# SW6106_C_LED.net
KiCad netlist of a schematic drawn in Altium Designer
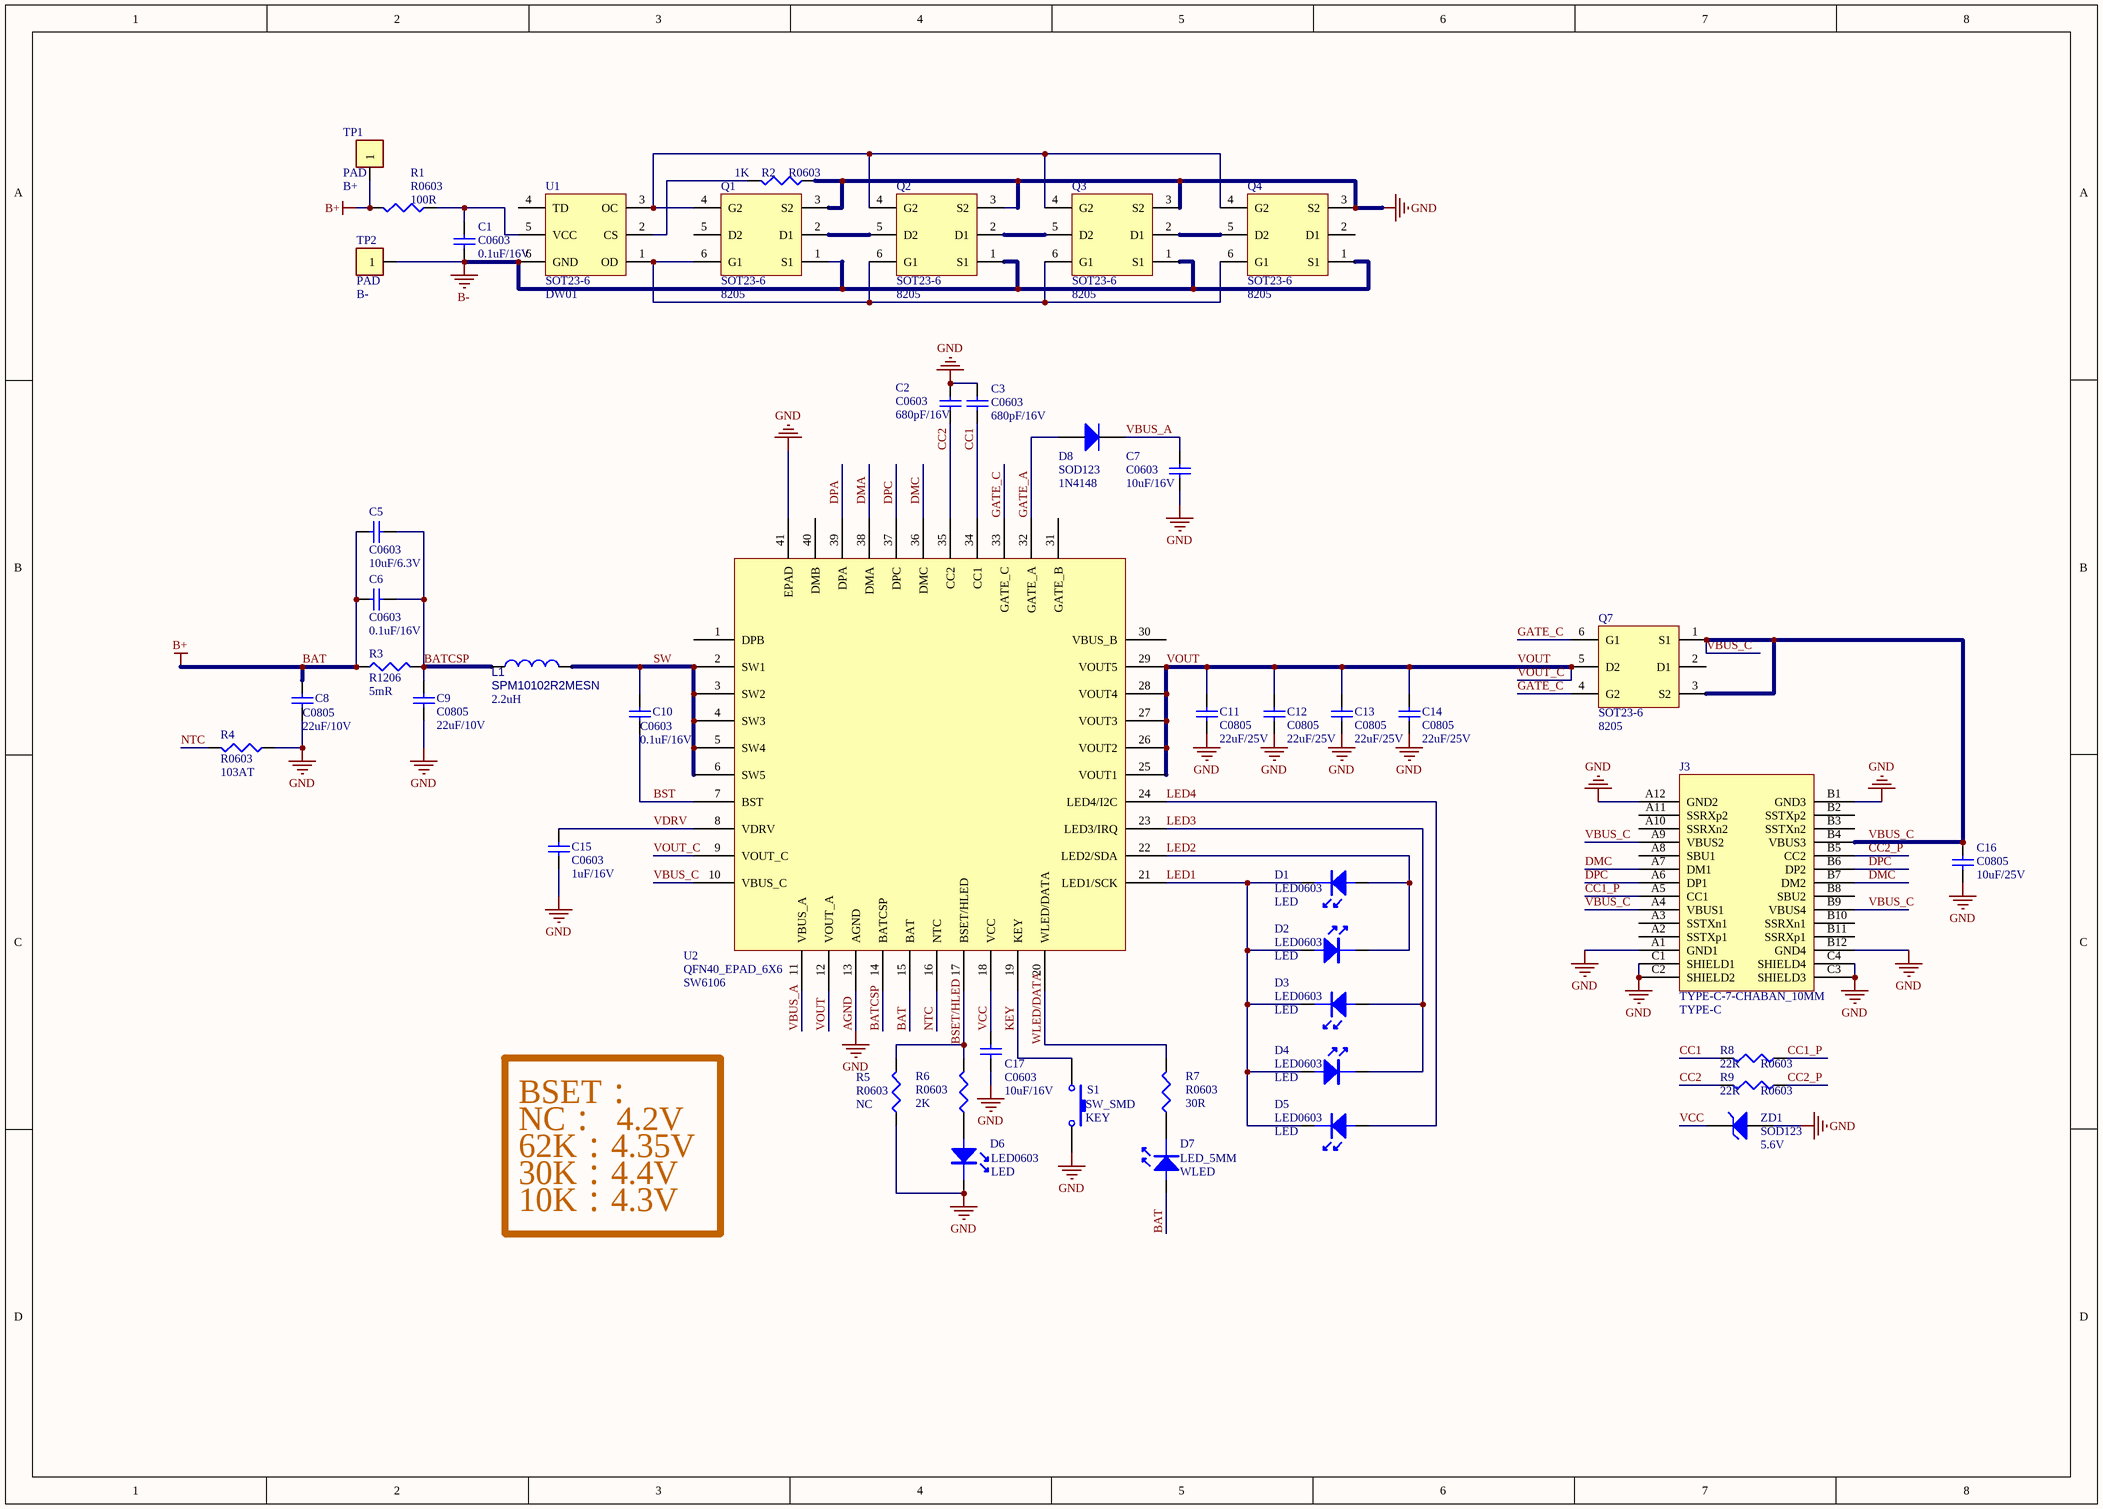
[diagram p0: SW6106+C+LED.SchDoc]

(export (version "E")
  (design (tool "Eeschema 10.0.6"))
  (components
    (comp (ref "C1")
      (value "C0603")
      (footprint "C0603")
      (description "Capacitor")
      (fields (field (name "ALTIUM_VALUE") "0.1uF/16V") (field (name "PUBLISHER") "Altium Limited"))
      (libsource (lib "*") (part "Cap"))
    )
    (comp (ref "C2")
      (value "C0603")
      (footprint "C0603")
      (description "Capacitor")
      (fields (field (name "ALTIUM_VALUE") "680pF/16V") (field (name "PUBLISHER") "Altium Limited"))
      (libsource (lib "*") (part "CAP0603"))
    )
    (comp (ref "C3")
      (value "C0603")
      (footprint "C0603")
      (description "Capacitor")
      (fields (field (name "ALTIUM_VALUE") "680pF/16V") (field (name "PUBLISHER") "Altium Limited"))
      (libsource (lib "*") (part "CAP0603"))
    )
    (comp (ref "C5")
      (value "C0603")
      (footprint "C0603")
      (description "Capacitor")
      (fields (field (name "ALTIUM_VALUE") "10uF/6.3V") (field (name "PUBLISHER") "Altium Limited"))
      (libsource (lib "*") (part "CAP0603"))
    )
    (comp (ref "C6")
      (value "C0603")
      (footprint "C0603")
      (description "Capacitor")
      (fields (field (name "ALTIUM_VALUE") "0.1uF/16V") (field (name "PUBLISHER") "Altium Limited"))
      (libsource (lib "*") (part "CAP0603"))
    )
    (comp (ref "C7")
      (value "C0603")
      (footprint "C0603")
      (description "Capacitor")
      (fields (field (name "ALTIUM_VALUE") "10uF/16V") (field (name "PUBLISHER") "Altium Limited"))
      (libsource (lib "*") (part "CAP0603"))
    )
    (comp (ref "C8")
      (value "C0805")
      (footprint "C0805")
      (description "Capacitor")
      (fields (field (name "ALTIUM_VALUE") "22uF/10V") (field (name "PUBLISHER") "Altium Limited"))
      (libsource (lib "*") (part "CAP0805"))
    )
    (comp (ref "C9")
      (value "C0805")
      (footprint "C0805")
      (description "Capacitor")
      (fields (field (name "ALTIUM_VALUE") "22uF/10V") (field (name "PUBLISHER") "Altium Limited"))
      (libsource (lib "*") (part "CAP0805"))
    )
    (comp (ref "C10")
      (value "C0603")
      (footprint "C0603")
      (description "Capacitor")
      (fields (field (name "ALTIUM_VALUE") "0.1uF/16V") (field (name "PUBLISHER") "Altium Limited"))
      (libsource (lib "*") (part "CAP0603"))
    )
    (comp (ref "C11")
      (value "C0805")
      (footprint "C0805")
      (description "Capacitor")
      (fields (field (name "ALTIUM_VALUE") "22uF/25V") (field (name "PUBLISHER") "Altium Limited"))
      (libsource (lib "*") (part "CAP0805"))
    )
    (comp (ref "C12")
      (value "C0805")
      (footprint "C0805")
      (description "Capacitor")
      (fields (field (name "ALTIUM_VALUE") "22uF/25V") (field (name "PUBLISHER") "Altium Limited"))
      (libsource (lib "*") (part "CAP0805"))
    )
    (comp (ref "C13")
      (value "C0805")
      (footprint "C0805")
      (description "Capacitor")
      (fields (field (name "ALTIUM_VALUE") "22uF/25V") (field (name "PUBLISHER") "Altium Limited"))
      (libsource (lib "*") (part "CAP0805"))
    )
    (comp (ref "C14")
      (value "C0805")
      (footprint "C0805")
      (description "Capacitor")
      (fields (field (name "ALTIUM_VALUE") "22uF/25V") (field (name "PUBLISHER") "Altium Limited"))
      (libsource (lib "*") (part "CAP0805"))
    )
    (comp (ref "C15")
      (value "C0603")
      (footprint "C0603")
      (description "Capacitor")
      (fields (field (name "ALTIUM_VALUE") "1uF/16V") (field (name "PUBLISHER") "Altium Limited"))
      (libsource (lib "*") (part "CAP0603"))
    )
    (comp (ref "C16")
      (value "C0805")
      (footprint "C0805")
      (description "Capacitor")
      (fields (field (name "ALTIUM_VALUE") "10uF/25V") (field (name "PUBLISHER") "Altium Limited"))
      (libsource (lib "*") (part "CAP0603"))
    )
    (comp (ref "C17")
      (value "C0603")
      (footprint "C0603")
      (description "Capacitor")
      (fields (field (name "ALTIUM_VALUE") "10uF/16V") (field (name "PUBLISHER") "Altium Limited"))
      (libsource (lib "*") (part "CAP0603"))
    )
    (comp (ref "D1") (value "LED") (footprint "LED0603") (libsource (lib "*") (part "LED")))
    (comp (ref "D2") (value "LED") (footprint "LED0603") (libsource (lib "*") (part "LED")))
    (comp (ref "D3") (value "LED") (footprint "LED0603") (libsource (lib "*") (part "LED")))
    (comp (ref "D4") (value "LED") (footprint "LED0603") (libsource (lib "*") (part "LED")))
    (comp (ref "D5") (value "LED") (footprint "LED0603") (libsource (lib "*") (part "LED")))
    (comp (ref "D6") (value "LED") (footprint "LED0603") (libsource (lib "*") (part "LED")))
    (comp (ref "D7")
      (value "WLED")
      (footprint "LED_5MM")
      (fields (field (name "FOOTPRINF") "LED_5MM") (field (name "Comment") "LED_5MM"))
      (libsource (lib "*") (part "LED"))
    )
    (comp (ref "D8")
      (value "1N4148")
      (footprint "SOD123")
      (description "High Conductance Fast Diode")
      (fields (field (name "Comment") "Diode 1N4148") (field (name "PUBLISHER") "Altium Limited"))
      (libsource (lib "Miscellaneous Devices") (part "Diode 1N4148"))
    )
    (comp (ref "J3")
      (value "TYPE-C")
      (footprint "TYPE-C-7-CHABAN_10MM")
      (libsource (lib "*") (part "TYPE-C"))
    )
    (comp (ref "L1")
      (value "SPM10102R2MESN")
      (footprint "INDUCTOR_SPM1010")
      (fields (field (name "ALTIUM_VALUE") "2.2uH"))
      (libsource (lib "*") (part "INDUCTOR"))
    )
    (comp (ref "Q1")
      (value "8205")
      (footprint "SOT23-6")
      (fields (field (name "FOOTPRINF") "SOT23-6"))
      (libsource (lib "*") (part "8205B"))
    )
    (comp (ref "Q2")
      (value "8205")
      (footprint "SOT23-6")
      (fields (field (name "FOOTPRINF") "SOT23-6"))
      (libsource (lib "*") (part "8205B"))
    )
    (comp (ref "Q3")
      (value "8205")
      (footprint "SOT23-6")
      (fields (field (name "FOOTPRINF") "SOT23-6"))
      (libsource (lib "*") (part "8205B"))
    )
    (comp (ref "Q4")
      (value "8205")
      (footprint "SOT23-6")
      (fields (field (name "FOOTPRINF") "SOT23-6"))
      (libsource (lib "*") (part "8205B"))
    )
    (comp (ref "Q7")
      (value "8205")
      (footprint "SOT23-6")
      (fields (field (name "FOOTPRINF") "SOT23-6"))
      (libsource (lib "") (part "8205B_1"))
    )
    (comp (ref "R1")
      (value "R0603")
      (footprint "R0603")
      (description "Resistor")
      (fields (field (name "ALTIUM_VALUE") "100R") (field (name "PUBLISHER") "Altium Limited"))
      (libsource (lib "*") (part "Res3"))
    )
    (comp (ref "R2")
      (value "R0603")
      (footprint "R0603")
      (description "Resistor")
      (fields (field (name "ALTIUM_VALUE") "1K") (field (name "PUBLISHER") "Altium Limited"))
      (libsource (lib "*") (part "Res3"))
    )
    (comp (ref "R3")
      (value "R1206")
      (footprint "R1206")
      (description "Resistor")
      (fields (field (name "ALTIUM_VALUE") "5mR") (field (name "PUBLISHER") "Altium Limited"))
      (libsource (lib "*") (part "RES"))
    )
    (comp (ref "R4")
      (value "R0603")
      (footprint "R0603")
      (description "Resistor")
      (fields (field (name "ALTIUM_VALUE") "103AT") (field (name "PUBLISHER") "Altium Limited"))
      (libsource (lib "*") (part "RES"))
    )
    (comp (ref "R5")
      (value "R0603")
      (footprint "R0603")
      (description "Resistor")
      (fields (field (name "ALTIUM_VALUE") "NC") (field (name "PUBLISHER") "Altium Limited"))
      (libsource (lib "*") (part "RES"))
    )
    (comp (ref "R6")
      (value "R0603")
      (footprint "R0603")
      (description "Resistor")
      (fields (field (name "ALTIUM_VALUE") "2K") (field (name "PUBLISHER") "Altium Limited"))
      (libsource (lib "*") (part "RES"))
    )
    (comp (ref "R7")
      (value "R0603")
      (footprint "R0603")
      (description "Resistor")
      (fields (field (name "ALTIUM_VALUE") "30R") (field (name "PUBLISHER") "Altium Limited"))
      (libsource (lib "*") (part "RES"))
    )
    (comp (ref "R8")
      (value "R0603")
      (footprint "R0603")
      (description "Resistor")
      (fields (field (name "ALTIUM_VALUE") "22R") (field (name "PUBLISHER") "Altium Limited"))
      (libsource (lib "*") (part "RES"))
    )
    (comp (ref "R9")
      (value "R0603")
      (footprint "R0603")
      (description "Resistor")
      (fields (field (name "ALTIUM_VALUE") "22R") (field (name "PUBLISHER") "Altium Limited"))
      (libsource (lib "*") (part "RES"))
    )
    (comp (ref "S1")
      (value "KEY")
      (footprint "SW_SMD")
      (fields (field (name "FOOTPRINF") "SW_SMD"))
      (libsource (lib "*") (part "SW K"))
    )
    (comp (ref "TP1") (value "B+") (footprint "PAD") (libsource (lib "*") (part "Test Point")))
    (comp (ref "TP2") (value "B-") (footprint "PAD") (libsource (lib "") (part "Test Point_1")))
    (comp (ref "U1")
      (value "DW01")
      (footprint "SOT23-6")
      (fields (field (name "FOOTPRINF") "SOT23-6"))
      (libsource (lib "*") (part "DW01"))
    )
    (comp (ref "U2")
      (value "SW6106")
      (footprint "QFN40_EPAD_6X6")
      (libsource (lib "TEST") (part "SW6106_AFC"))
    )
    (comp (ref "ZD1")
      (value "SOD123")
      (footprint "SOD-123")
      (description "Zener Diode")
      (fields (field (name "ALTIUM_UNNAMED_1") "5.6V"))
      (libsource (lib "Miscellaneous Devices") (part "D Zener"))
    )
  )
  (nets
    (net (code "1") (name "/BATCSP") (class "Default")
      (node (ref "C5") (pin "2") (pinfunction "2_2") (pintype "passive"))
      (node (ref "C6") (pin "2") (pinfunction "2_2") (pintype "passive"))
      (node (ref "C9") (pin "2") (pinfunction "2_2") (pintype "passive"))
      (node (ref "L1") (pin "1") (pinfunction "1_1") (pintype "passive"))
      (node (ref "R3") (pin "2") (pinfunction "2_2") (pintype "passive"))
      (node (ref "U2") (pin "14") (pinfunction "BATCSP_14") (pintype "passive"))
    )
    (net (code "2") (name "/BSET{slash}HLED") (class "Default")
      (node (ref "R5") (pin "2") (pinfunction "2_2") (pintype "passive"))
      (node (ref "R6") (pin "2") (pinfunction "2_2") (pintype "passive"))
      (node (ref "U2") (pin "17") (pinfunction "BSET/HLED_17") (pintype "passive"))
    )
    (net (code "3") (name "/BST") (class "Default")
      (node (ref "C10") (pin "1") (pinfunction "1_1") (pintype "passive"))
      (node (ref "U2") (pin "7") (pinfunction "BST_7") (pintype "passive"))
    )
    (net (code "4") (name "/CC1") (class "Default")
      (node (ref "C3") (pin "1") (pinfunction "1_1") (pintype "passive"))
      (node (ref "R8") (pin "2") (pinfunction "2_2") (pintype "passive"))
      (node (ref "U2") (pin "34") (pinfunction "CC1_34") (pintype "passive"))
    )
    (net (code "5") (name "/CC1_P") (class "Default")
      (node (ref "J3") (pin "A5") (pinfunction "CC1_A5") (pintype "passive"))
      (node (ref "R8") (pin "1") (pinfunction "1_1") (pintype "passive"))
    )
    (net (code "6") (name "/CC2") (class "Default")
      (node (ref "C2") (pin "1") (pinfunction "1_1") (pintype "passive"))
      (node (ref "R9") (pin "2") (pinfunction "2_2") (pintype "passive"))
      (node (ref "U2") (pin "35") (pinfunction "CC2_35") (pintype "passive"))
    )
    (net (code "7") (name "/CC2_P") (class "Default")
      (node (ref "J3") (pin "B5") (pinfunction "CC2_B5") (pintype "passive"))
      (node (ref "R9") (pin "1") (pinfunction "1_1") (pintype "passive"))
    )
    (net (code "8") (name "/DMA") (class "Default")
      (node (ref "U2") (pin "38") (pinfunction "DMA_38") (pintype "passive"))
    )
    (net (code "9") (name "/DMC") (class "Default")
      (node (ref "J3") (pin "A7") (pinfunction "DM1_A7") (pintype "passive"))
      (node (ref "J3") (pin "B7") (pinfunction "DM2_B7") (pintype "passive"))
      (node (ref "U2") (pin "36") (pinfunction "DMC_36") (pintype "passive"))
    )
    (net (code "10") (name "/DPA") (class "Default")
      (node (ref "U2") (pin "39") (pinfunction "DPA_39") (pintype "passive"))
    )
    (net (code "11") (name "/DPC") (class "Default")
      (node (ref "J3") (pin "A6") (pinfunction "DP1_A6") (pintype "passive"))
      (node (ref "J3") (pin "B6") (pinfunction "DP2_B6") (pintype "passive"))
      (node (ref "U2") (pin "37") (pinfunction "DPC_37") (pintype "passive"))
    )
    (net (code "12") (name "/GATE_A") (class "Default")
      (node (ref "D8") (pin "1") (pinfunction "A_1") (pintype "passive"))
      (node (ref "U2") (pin "32") (pinfunction "GATE_A_32") (pintype "passive"))
    )
    (net (code "13") (name "/GATE_C") (class "Default")
      (node (ref "Q7") (pin "4") (pinfunction "G2_4") (pintype "passive"))
      (node (ref "Q7") (pin "6") (pinfunction "G1_6") (pintype "passive"))
      (node (ref "U2") (pin "33") (pinfunction "GATE_C_33") (pintype "passive"))
    )
    (net (code "14") (name "/KEY") (class "Default")
      (node (ref "S1") (pin "1") (pinfunction "1_1") (pintype "passive"))
      (node (ref "U2") (pin "19") (pinfunction "KEY_19") (pintype "passive"))
    )
    (net (code "15") (name "/LED1") (class "Default")
      (node (ref "D1") (pin "2") (pinfunction "K_2") (pintype "passive"))
      (node (ref "D2") (pin "1") (pinfunction "A_1") (pintype "passive"))
      (node (ref "D3") (pin "2") (pinfunction "K_2") (pintype "passive"))
      (node (ref "D4") (pin "1") (pinfunction "A_1") (pintype "passive"))
      (node (ref "D5") (pin "2") (pinfunction "K_2") (pintype "passive"))
      (node (ref "U2") (pin "21") (pinfunction "LED1/SCK_21") (pintype "passive"))
    )
    (net (code "16") (name "/LED2") (class "Default")
      (node (ref "D1") (pin "1") (pinfunction "A_1") (pintype "passive"))
      (node (ref "D2") (pin "2") (pinfunction "K_2") (pintype "passive"))
      (node (ref "U2") (pin "22") (pinfunction "LED2/SDA_22") (pintype "passive"))
    )
    (net (code "17") (name "/LED3") (class "Default")
      (node (ref "D3") (pin "1") (pinfunction "A_1") (pintype "passive"))
      (node (ref "D4") (pin "2") (pinfunction "K_2") (pintype "passive"))
      (node (ref "U2") (pin "23") (pinfunction "LED3/IRQ_23") (pintype "passive"))
    )
    (net (code "18") (name "/LED4") (class "Default")
      (node (ref "D5") (pin "1") (pinfunction "A_1") (pintype "passive"))
      (node (ref "U2") (pin "24") (pinfunction "LED4/I2C_24") (pintype "passive"))
    )
    (net (code "19") (name "/NTC") (class "Default")
      (node (ref "R4") (pin "2") (pinfunction "2_2") (pintype "passive"))
      (node (ref "U2") (pin "16") (pinfunction "NTC_16") (pintype "passive"))
    )
    (net (code "20") (name "/SW") (class "Default")
      (node (ref "C10") (pin "2") (pinfunction "2_2") (pintype "passive"))
      (node (ref "L1") (pin "2") (pinfunction "2_2") (pintype "passive"))
      (node (ref "U2") (pin "2") (pinfunction "SW1_2") (pintype "passive"))
      (node (ref "U2") (pin "3") (pinfunction "SW2_3") (pintype "passive"))
      (node (ref "U2") (pin "4") (pinfunction "SW3_4") (pintype "passive"))
      (node (ref "U2") (pin "5") (pinfunction "SW4_5") (pintype "passive"))
      (node (ref "U2") (pin "6") (pinfunction "SW5_6") (pintype "passive"))
    )
    (net (code "21") (name "/VBUS_A") (class "Default")
      (node (ref "C7") (pin "2") (pinfunction "2_2") (pintype "passive"))
      (node (ref "D8") (pin "2") (pinfunction "K_2") (pintype "passive"))
      (node (ref "U2") (pin "11") (pinfunction "VBUS_A_11") (pintype "passive"))
    )
    (net (code "22") (name "/VBUS_C") (class "Default")
      (node (ref "C16") (pin "2") (pinfunction "2_2") (pintype "passive"))
      (node (ref "J3") (pin "A4") (pinfunction "VBUS1_A4") (pintype "passive"))
      (node (ref "J3") (pin "A9") (pinfunction "VBUS2_A9") (pintype "passive"))
      (node (ref "J3") (pin "B4") (pinfunction "VBUS3_B4") (pintype "passive"))
      (node (ref "J3") (pin "B9") (pinfunction "VBUS4_B9") (pintype "passive"))
      (node (ref "Q7") (pin "1") (pinfunction "S1_1") (pintype "passive"))
      (node (ref "Q7") (pin "3") (pinfunction "S2_3") (pintype "passive"))
      (node (ref "U2") (pin "10") (pinfunction "VBUS_C_10") (pintype "passive"))
    )
    (net (code "23") (name "/VCC") (class "Default")
      (node (ref "C17") (pin "2") (pinfunction "2_2") (pintype "passive"))
      (node (ref "U2") (pin "18") (pinfunction "VCC_18") (pintype "passive"))
      (node (ref "ZD1") (pin "2") (pinfunction "K_2") (pintype "passive"))
    )
    (net (code "24") (name "/VDRV") (class "Default")
      (node (ref "C15") (pin "2") (pinfunction "2_2") (pintype "passive"))
      (node (ref "U2") (pin "8") (pinfunction "VDRV_8") (pintype "passive"))
    )
    (net (code "25") (name "/VOUT") (class "Default")
      (node (ref "C11") (pin "2") (pinfunction "2_2") (pintype "passive"))
      (node (ref "C12") (pin "2") (pinfunction "2_2") (pintype "passive"))
      (node (ref "C13") (pin "2") (pinfunction "2_2") (pintype "passive"))
      (node (ref "C14") (pin "2") (pinfunction "2_2") (pintype "passive"))
      (node (ref "Q7") (pin "5") (pinfunction "D2_5") (pintype "passive"))
      (node (ref "U2") (pin "12") (pinfunction "VOUT_A_12") (pintype "passive"))
      (node (ref "U2") (pin "25") (pinfunction "VOUT1_25") (pintype "passive"))
      (node (ref "U2") (pin "26") (pinfunction "VOUT2_26") (pintype "passive"))
      (node (ref "U2") (pin "27") (pinfunction "VOUT3_27") (pintype "passive"))
      (node (ref "U2") (pin "28") (pinfunction "VOUT4_28") (pintype "passive"))
      (node (ref "U2") (pin "29") (pinfunction "VOUT5_29") (pintype "passive"))
      (node (ref "U2") (pin "9") (pinfunction "VOUT_C_9") (pintype "passive"))
    )
    (net (code "26") (name "/WLED{slash}DATA") (class "Default")
      (node (ref "R7") (pin "2") (pinfunction "2_2") (pintype "passive"))
      (node (ref "U2") (pin "20") (pinfunction "WLED/DATA_20") (pintype "passive"))
    )
    (net (code "27") (name "B+") (class "Default")
      (node (ref "C5") (pin "1") (pinfunction "1_1") (pintype "passive"))
      (node (ref "C6") (pin "1") (pinfunction "1_1") (pintype "passive"))
      (node (ref "C8") (pin "2") (pinfunction "2_2") (pintype "passive"))
      (node (ref "D7") (pin "1") (pinfunction "A_1") (pintype "passive"))
      (node (ref "R1") (pin "2") (pinfunction "2_2") (pintype "passive"))
      (node (ref "R3") (pin "1") (pinfunction "1_1") (pintype "passive"))
      (node (ref "TP1") (pin "1") (pinfunction "1_1") (pintype "passive"))
      (node (ref "U2") (pin "15") (pinfunction "BAT_15") (pintype "passive"))
    )
    (net (code "28") (name "B-") (class "Default")
      (node (ref "C1") (pin "1") (pinfunction "1_1") (pintype "passive"))
      (node (ref "Q1") (pin "1") (pinfunction "S1_1") (pintype "passive"))
      (node (ref "Q2") (pin "1") (pinfunction "S1_1") (pintype "passive"))
      (node (ref "Q3") (pin "1") (pinfunction "S1_1") (pintype "passive"))
      (node (ref "Q4") (pin "1") (pinfunction "S1_1") (pintype "passive"))
      (node (ref "TP2") (pin "1") (pinfunction "1_1") (pintype "passive"))
      (node (ref "U1") (pin "6") (pinfunction "GND_6") (pintype "passive"))
    )
    (net (code "29") (name "GND") (class "Default")
      (node (ref "C11") (pin "1") (pinfunction "1_1") (pintype "passive"))
      (node (ref "C12") (pin "1") (pinfunction "1_1") (pintype "passive"))
      (node (ref "C13") (pin "1") (pinfunction "1_1") (pintype "passive"))
      (node (ref "C14") (pin "1") (pinfunction "1_1") (pintype "passive"))
      (node (ref "C15") (pin "1") (pinfunction "1_1") (pintype "passive"))
      (node (ref "C16") (pin "1") (pinfunction "1_1") (pintype "passive"))
      (node (ref "C17") (pin "1") (pinfunction "1_1") (pintype "passive"))
      (node (ref "C2") (pin "2") (pinfunction "2_2") (pintype "passive"))
      (node (ref "C3") (pin "2") (pinfunction "2_2") (pintype "passive"))
      (node (ref "C7") (pin "1") (pinfunction "1_1") (pintype "passive"))
      (node (ref "C8") (pin "1") (pinfunction "1_1") (pintype "passive"))
      (node (ref "C9") (pin "1") (pinfunction "1_1") (pintype "passive"))
      (node (ref "D6") (pin "2") (pinfunction "K_2") (pintype "passive"))
      (node (ref "J3") (pin "A1") (pinfunction "GND1_A1") (pintype "passive"))
      (node (ref "J3") (pin "A12") (pinfunction "GND2_A12") (pintype "passive"))
      (node (ref "J3") (pin "B1") (pinfunction "GND3_B1") (pintype "passive"))
      (node (ref "J3") (pin "B12") (pinfunction "GND4_B12") (pintype "passive"))
      (node (ref "J3") (pin "C1") (pinfunction "SHIELD1_C1") (pintype "passive"))
      (node (ref "J3") (pin "C2") (pinfunction "SHIELD2_C2") (pintype "passive"))
      (node (ref "J3") (pin "C3") (pinfunction "SHIELD3_C3") (pintype "passive"))
      (node (ref "J3") (pin "C4") (pinfunction "SHIELD4_C4") (pintype "passive"))
      (node (ref "Q1") (pin "3") (pinfunction "S2_3") (pintype "passive"))
      (node (ref "Q2") (pin "3") (pinfunction "S2_3") (pintype "passive"))
      (node (ref "Q3") (pin "3") (pinfunction "S2_3") (pintype "passive"))
      (node (ref "Q4") (pin "3") (pinfunction "S2_3") (pintype "passive"))
      (node (ref "R2") (pin "1") (pinfunction "1_1") (pintype "passive"))
      (node (ref "R4") (pin "1") (pinfunction "1_1") (pintype "passive"))
      (node (ref "R5") (pin "1") (pinfunction "1_1") (pintype "passive"))
      (node (ref "S1") (pin "2") (pinfunction "2_2") (pintype "passive"))
      (node (ref "U2") (pin "13") (pinfunction "AGND_13") (pintype "passive"))
      (node (ref "U2") (pin "41") (pinfunction "EPAD_41") (pintype "passive"))
      (node (ref "ZD1") (pin "1") (pinfunction "A_1") (pintype "passive"))
    )
    (net (code "30") (name "Net-(D6-A)") (class "Default")
      (node (ref "D6") (pin "1") (pinfunction "A_1") (pintype "passive"))
      (node (ref "R6") (pin "1") (pinfunction "1_1") (pintype "passive"))
    )
    (net (code "31") (name "Net-(D7-K)") (class "Default")
      (node (ref "D7") (pin "2") (pinfunction "K_2") (pintype "passive"))
      (node (ref "R7") (pin "1") (pinfunction "1_1") (pintype "passive"))
    )
    (net (code "32") (name "Net-(Q1-D1)") (class "Default")
      (node (ref "Q1") (pin "2") (pinfunction "D1_2") (pintype "passive"))
      (node (ref "Q2") (pin "5") (pinfunction "D2_5") (pintype "passive"))
    )
    (net (code "33") (name "Net-(Q1-G1)") (class "Default")
      (node (ref "Q1") (pin "6") (pinfunction "G1_6") (pintype "passive"))
      (node (ref "Q2") (pin "6") (pinfunction "G1_6") (pintype "passive"))
      (node (ref "Q3") (pin "6") (pinfunction "G1_6") (pintype "passive"))
      (node (ref "Q4") (pin "6") (pinfunction "G1_6") (pintype "passive"))
      (node (ref "U1") (pin "1") (pinfunction "OD_1") (pintype "passive"))
    )
    (net (code "34") (name "Net-(Q1-G2)") (class "Default")
      (node (ref "Q1") (pin "4") (pinfunction "G2_4") (pintype "passive"))
      (node (ref "Q2") (pin "4") (pinfunction "G2_4") (pintype "passive"))
      (node (ref "Q3") (pin "4") (pinfunction "G2_4") (pintype "passive"))
      (node (ref "Q4") (pin "4") (pinfunction "G2_4") (pintype "passive"))
      (node (ref "U1") (pin "3") (pinfunction "OC_3") (pintype "passive"))
    )
    (net (code "35") (name "Net-(Q2-D1)") (class "Default")
      (node (ref "Q2") (pin "2") (pinfunction "D1_2") (pintype "passive"))
      (node (ref "Q3") (pin "5") (pinfunction "D2_5") (pintype "passive"))
    )
    (net (code "36") (name "Net-(Q3-D1)") (class "Default")
      (node (ref "Q3") (pin "2") (pinfunction "D1_2") (pintype "passive"))
      (node (ref "Q4") (pin "5") (pinfunction "D2_5") (pintype "passive"))
    )
    (net (code "37") (name "Net-(U1-CS)") (class "Default")
      (node (ref "R2") (pin "2") (pinfunction "2_2") (pintype "passive"))
      (node (ref "U1") (pin "2") (pinfunction "CS_2") (pintype "passive"))
    )
    (net (code "38") (name "Net-(U1-VCC)") (class "Default")
      (node (ref "C1") (pin "2") (pinfunction "2_2") (pintype "passive"))
      (node (ref "R1") (pin "1") (pinfunction "1_1") (pintype "passive"))
      (node (ref "U1") (pin "5") (pinfunction "VCC_5") (pintype "passive"))
    )
    (net (code "39") (name "unconnected-(J3-SBU1-PadA8)") (class "Default")
      (node (ref "J3") (pin "A8") (pinfunction "SBU1_A8") (pintype "passive"))
    )
    (net (code "40") (name "unconnected-(J3-SBU2-PadB8)") (class "Default")
      (node (ref "J3") (pin "B8") (pinfunction "SBU2_B8") (pintype "passive"))
    )
    (net (code "41") (name "unconnected-(J3-SSRXn1-PadB10)") (class "Default")
      (node (ref "J3") (pin "B10") (pinfunction "SSRXn1_B10") (pintype "passive"))
    )
    (net (code "42") (name "unconnected-(J3-SSRXn2-PadA10)") (class "Default")
      (node (ref "J3") (pin "A10") (pinfunction "SSRXn2_A10") (pintype "passive"))
    )
    (net (code "43") (name "unconnected-(J3-SSRXp1-PadB11)") (class "Default")
      (node (ref "J3") (pin "B11") (pinfunction "SSRXp1_B11") (pintype "passive"))
    )
    (net (code "44") (name "unconnected-(J3-SSRXp2-PadA11)") (class "Default")
      (node (ref "J3") (pin "A11") (pinfunction "SSRXp2_A11") (pintype "passive"))
    )
    (net (code "45") (name "unconnected-(J3-SSTXn1-PadA3)") (class "Default")
      (node (ref "J3") (pin "A3") (pinfunction "SSTXn1_A3") (pintype "passive"))
    )
    (net (code "46") (name "unconnected-(J3-SSTXn2-PadB3)") (class "Default")
      (node (ref "J3") (pin "B3") (pinfunction "SSTXn2_B3") (pintype "passive"))
    )
    (net (code "47") (name "unconnected-(J3-SSTXp1-PadA2)") (class "Default")
      (node (ref "J3") (pin "A2") (pinfunction "SSTXp1_A2") (pintype "passive"))
    )
    (net (code "48") (name "unconnected-(J3-SSTXp2-PadB2)") (class "Default")
      (node (ref "J3") (pin "B2") (pinfunction "SSTXp2_B2") (pintype "passive"))
    )
    (net (code "49") (name "unconnected-(Q1-D2-Pad5)") (class "Default")
      (node (ref "Q1") (pin "5") (pinfunction "D2_5") (pintype "passive"))
    )
    (net (code "50") (name "unconnected-(Q4-D1-Pad2)") (class "Default")
      (node (ref "Q4") (pin "2") (pinfunction "D1_2") (pintype "passive"))
    )
    (net (code "51") (name "unconnected-(Q7-D1-Pad2)") (class "Default")
      (node (ref "Q7") (pin "2") (pinfunction "D1_2") (pintype "passive"))
    )
    (net (code "52") (name "unconnected-(U1-TD-Pad4)") (class "Default")
      (node (ref "U1") (pin "4") (pinfunction "TD_4") (pintype "passive"))
    )
    (net (code "53") (name "unconnected-(U2-DMB-Pad40)") (class "Default")
      (node (ref "U2") (pin "40") (pinfunction "DMB_40") (pintype "passive"))
    )
    (net (code "54") (name "unconnected-(U2-DPB-Pad1)") (class "Default")
      (node (ref "U2") (pin "1") (pinfunction "DPB_1") (pintype "passive"))
    )
    (net (code "55") (name "unconnected-(U2-GATE_B-Pad31)") (class "Default")
      (node (ref "U2") (pin "31") (pinfunction "GATE_B_31") (pintype "passive"))
    )
    (net (code "56") (name "unconnected-(U2-VBUS_B-Pad30)") (class "Default")
      (node (ref "U2") (pin "30") (pinfunction "VBUS_B_30") (pintype "passive"))
    )
  )
)
